# mcu.net
KiCad netlist of a schematic drawn in Altium Designer
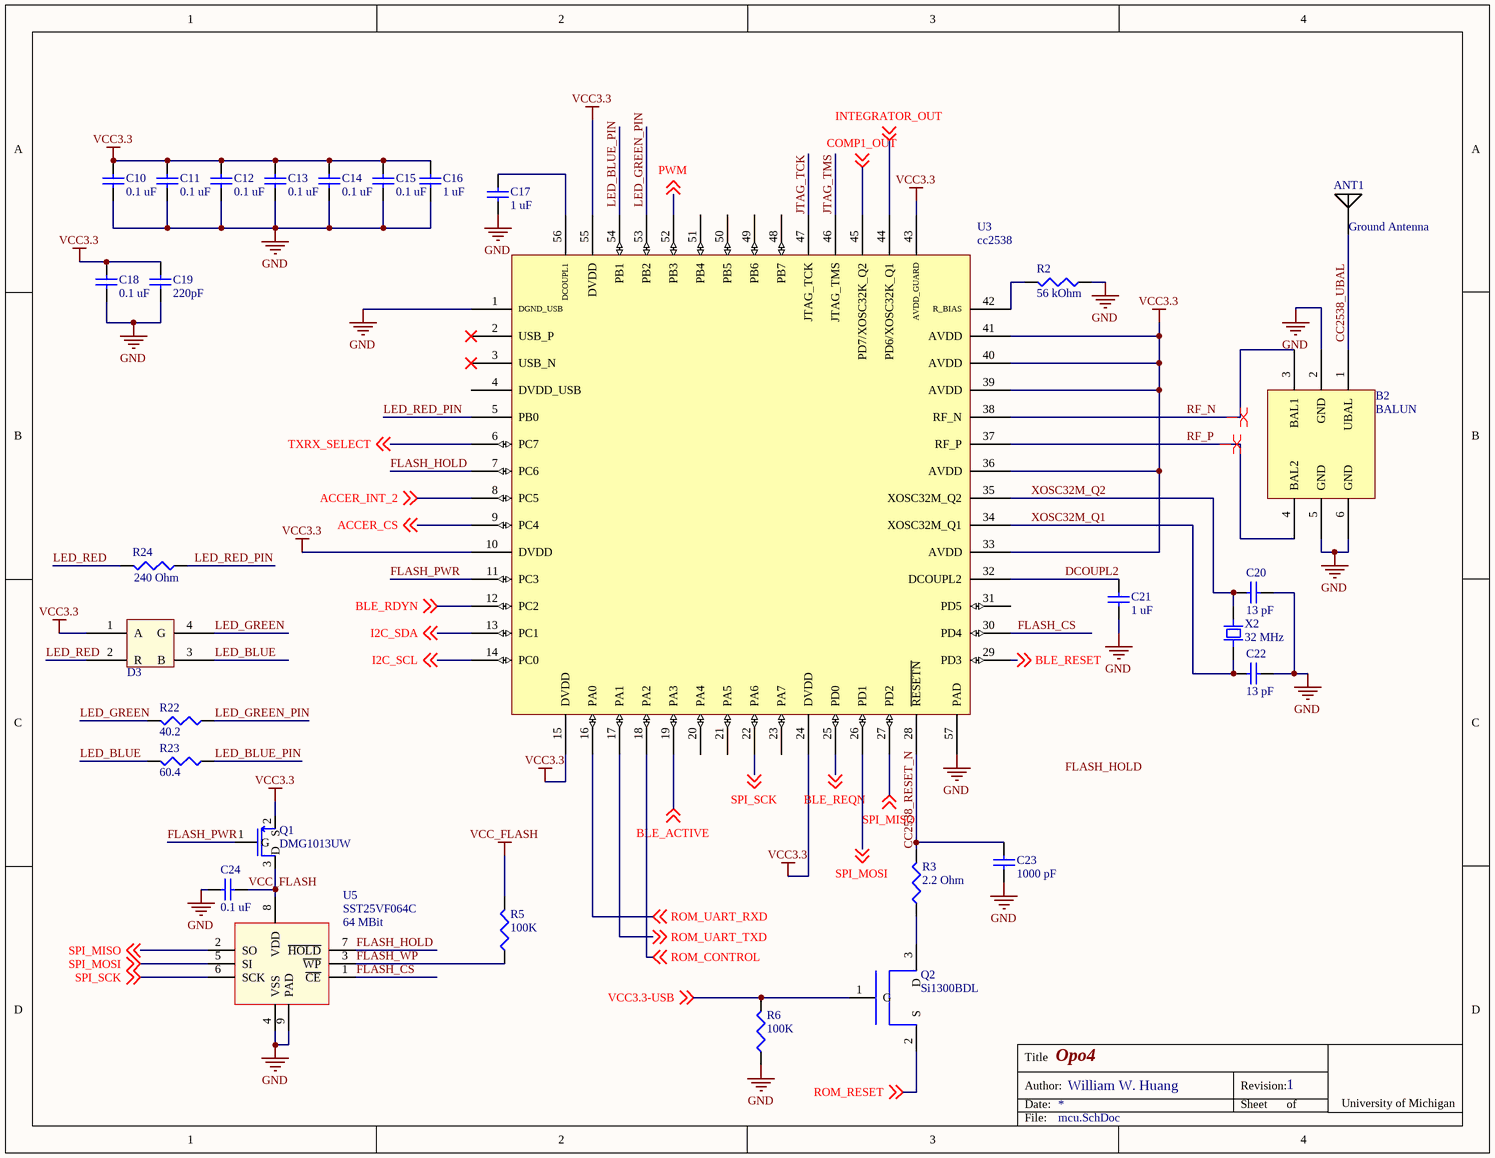
[diagram p0: mcu.SchDoc]

(export (version "E")
  (design (tool "Eeschema 10.0.6"))
  (components
    (comp (ref "ANT1")
      (value "Ground Antenna")
      (footprint "SMD Ground Antenna")
      (description "Molex 2.4 GHz SMD On-Ground Antenna")
      (libsource (lib "opo_general") (part "Molex Antenna"))
    )
    (comp (ref "B2")
      (value "BALUN")
      (footprint "2450BM15A0002")
      (description "Johanson CC253X Balun")
      (fields (field (name "MFR") "Johanson Technology") (field (name "MFR PART NUMBER") "2450BM15A0002"))
      (libsource (lib "opo_general") (part "cc2538_Balun"))
    )
    (comp (ref "C10")
      (value "0.1 uF")
      (footprint "0402")
      (description "Ceramic capacitor, 0.1u, 0402 package")
      (fields (field (name "TOLERANCE") "10%") (field (name "Comment") "Ceramic capacitor"))
      (libsource (lib "rlc") (part "C_0.1u_0402_ceramic"))
    )
    (comp (ref "C11")
      (value "0.1 uF")
      (footprint "0402")
      (description "Ceramic capacitor, 0.1u, 0402 package")
      (fields (field (name "TOLERANCE") "10%") (field (name "Comment") "Ceramic capacitor"))
      (libsource (lib "rlc") (part "C_0.1u_0402_ceramic"))
    )
    (comp (ref "C12")
      (value "0.1 uF")
      (footprint "0402")
      (description "Ceramic capacitor, 0.1u, 0402 package")
      (fields (field (name "TOLERANCE") "10%") (field (name "Comment") "Ceramic capacitor"))
      (libsource (lib "rlc") (part "C_0.1u_0402_ceramic"))
    )
    (comp (ref "C13")
      (value "0.1 uF")
      (footprint "0402")
      (description "Ceramic capacitor, 0.1u, 0402 package")
      (fields (field (name "TOLERANCE") "10%") (field (name "Comment") "Ceramic capacitor"))
      (libsource (lib "rlc") (part "C_0.1u_0402_ceramic"))
    )
    (comp (ref "C14")
      (value "0.1 uF")
      (footprint "0402")
      (description "Ceramic capacitor, 0.1u, 0402 package")
      (fields (field (name "TOLERANCE") "10%") (field (name "Comment") "Ceramic capacitor"))
      (libsource (lib "rlc") (part "C_0.1u_0402_ceramic"))
    )
    (comp (ref "C15")
      (value "0.1 uF")
      (footprint "0402")
      (description "Ceramic capacitor, 0.1u, 0402 package")
      (fields (field (name "TOLERANCE") "10%") (field (name "Comment") "Ceramic capacitor"))
      (libsource (lib "rlc") (part "C_0.1u_0402_ceramic"))
    )
    (comp (ref "C16")
      (value "1 uF")
      (footprint "0402")
      (description "Ceramic capacitor, 1 uF, 0402 package")
      (fields (field (name "TOLERANCE") "10%") (field (name "Comment") "Ceramic capacitor"))
      (libsource (lib "rlc") (part "C_1u_0402_ceramic"))
    )
    (comp (ref "C17")
      (value "1 uF")
      (footprint "0402")
      (description "Ceramic capacitor, 1 uF, 0402 package")
      (fields (field (name "TOLERANCE") "10%") (field (name "Comment") "Ceramic capacitor"))
      (libsource (lib "rlc") (part "C_1u_0402_ceramic"))
    )
    (comp (ref "C18")
      (value "0.1 uF")
      (footprint "0402")
      (description "Ceramic capacitor, 0.1u, 0402 package")
      (fields (field (name "TOLERANCE") "10%") (field (name "Comment") "Ceramic capacitor"))
      (libsource (lib "rlc") (part "C_0.1u_0402_ceramic"))
    )
    (comp (ref "C19")
      (value "220pF")
      (footprint "0402")
      (description "220pF 5% 50 V C0G NP0 0402 ceramic cap")
      (fields (field (name "MFR") "Murata") (field (name "MFR PART NUMBER") "GRM1555C1H221JA01D"))
      (libsource (lib "rlc") (part "C_220pf_0402_ceramic"))
    )
    (comp (ref "C20")
      (value "13 pF")
      (footprint "0402")
      (description "13pf, 50V, 2%, c0G, NP0, 0402, ceramic")
      (fields (field (name "MFR") "Murata") (field (name "MFR PART NUMBER") "GRM1555C1H130GA01D"))
      (libsource (lib "rlc") (part "C_13p_0402"))
    )
    (comp (ref "C21")
      (value "1 uF")
      (footprint "0402")
      (description "Ceramic capacitor, 1 uF, 0402 package")
      (fields (field (name "TOLERANCE") "10%") (field (name "Comment") "Ceramic capacitor"))
      (libsource (lib "rlc") (part "C_1u_0402_ceramic"))
    )
    (comp (ref "C22")
      (value "13 pF")
      (footprint "0402")
      (description "13pf, 50V, 2%, c0G, NP0, 0402, ceramic")
      (fields (field (name "MFR") "Murata") (field (name "MFR PART NUMBER") "GRM1555C1H130GA01D"))
      (libsource (lib "rlc") (part "C_13p_0402"))
    )
    (comp (ref "C23")
      (value "1000 pF")
      (footprint "0402")
      (description "Ceramic capacitor, 1000 pF, 0402 package")
      (fields (field (name "TOLERANCE") "10%") (field (name "Comment") "Ceramic capacitor"))
      (libsource (lib "rlc") (part "C_1000p_0402_ceramic"))
    )
    (comp (ref "C24")
      (value "0.1 uF")
      (footprint "0402")
      (description "Ceramic capacitor, 0.1u, 0402 package")
      (fields (field (name "TOLERANCE") "10%") (field (name "Comment") "Ceramic capacitor"))
      (libsource (lib "rlc") (part "C_0.1u_0402_ceramic"))
    )
    (comp (ref "D3")
      (value "Tri Color LED")
      (footprint "0404")
      (description "LED, RGB, 0404")
      (libsource (lib "rlc") (part "D_LED_RGB_0404"))
    )
    (comp (ref "Q1")
      (value "DMG1013UW")
      (footprint "SC70-3")
      (description "P-CHANNEL ENHANCEMENT MODE MOSFET")
      (libsource (lib "opo_general") (part "DMG1013UW"))
    )
    (comp (ref "Q2")
      (value "Si1300BDL")
      (footprint "SC70-3")
      (description "MOSFET N-CH D-S 20V SC-70-3")
      (libsource (lib "opo_general") (part "Si1300BDL"))
    )
    (comp (ref "R2")
      (value "56 kOhm")
      (footprint "0402")
      (description "56 kOhm, 1%, .0603 W, 0402")
      (fields (field (name "MFR") "Rohm") (field (name "MFR PART NUMBER") "MCR01MRTF5602"))
      (libsource (lib "rlc") (part "R_56K_0402"))
    )
    (comp (ref "R3")
      (value "2.2 Ohm")
      (footprint "0402")
      (description "2.2 Ohm, 1%, .063W, 0402")
      (fields (field (name "MFR") "Vishay Dale") (field (name "MFR PART NUMBER") "CRCW04022R20FKED"))
      (libsource (lib "rlc") (part "R_2.2_0402"))
    )
    (comp (ref "R5")
      (value "100K")
      (footprint "0402")
      (description "Chip resistor, 100K, 0402 package")
      (fields (field (name "TOLERANCE") "1%") (field (name "POWER") "1/16 W"))
      (libsource (lib "rlc") (part "R_100K_0402"))
    )
    (comp (ref "R6")
      (value "100K")
      (footprint "0402")
      (description "Chip resistor, 100K, 0402 package")
      (fields (field (name "TOLERANCE") "1%") (field (name "POWER") "1/16 W"))
      (libsource (lib "rlc") (part "R_100K_0402"))
    )
    (comp (ref "R22")
      (value "40.2")
      (footprint "0201")
      (description "40.2 Ohm 0201 1% Chip Resistor")
      (fields (field (name "Comment") "Chip Resistor"))
      (libsource (lib "rlc") (part "R_40.2_0201"))
    )
    (comp (ref "R23")
      (value "60.4")
      (footprint "0201")
      (description "60.4 Ohm, .05W, 1% 0201 Chip Resistor")
      (fields (field (name "Comment") "Chip resistor"))
      (libsource (lib "rlc") (part "R_60.4_0201"))
    )
    (comp (ref "R24")
      (value "240 Ohm")
      (footprint "0201")
      (description "240 Ohm, 1%, .05W, 0201 Chip Resistor")
      (fields (field (name "Comment") "Chip resistor"))
      (libsource (lib "rlc") (part "R_240_0201"))
    )
    (comp (ref "U3")
      (value "cc2538")
      (footprint "QFN50P800X800X100_HS-57N")
      (description "cc2538 MCU/802.15.4 radio")
      (libsource (lib "opo_general") (part "cc2538"))
    )
    (comp (ref "U5")
      (value "SST25VF064C")
      (footprint "WSON")
      (description "64 Mbit SPI Serial Dual I/O Flash")
      (fields (field (name "CAPACITY") "64 MBit"))
      (libsource (lib "opo_general") (part "SST25VF064C"))
    )
    (comp (ref "X2")
      (value "32 MHz")
      (footprint "FA-128")
      (description "32MHz, 10ppm, 10pF, 60 Ohm")
      (fields (field (name "MFR") "Epson") (field (name "MFR PART NUMBER") "FA-128 32.0000MF20X-K3"))
      (libsource (lib "opo_general") (part "X_32M_FA-128"))
    )
  )
  (nets
    (net (code "1") (name "/CC2538_RESET_N") (class "Default")
      (node (ref "C23") (pin "1") (pintype "passive"))
      (node (ref "R3") (pin "1") (pintype "passive"))
      (node (ref "U3") (pin "28") (pinfunction "~{RESETN}_28") (pintype "passive"))
    )
    (net (code "2") (name "/CC2538_UBAL") (class "Default")
      (node (ref "ANT1") (pin "1") (pintype "passive"))
      (node (ref "B2") (pin "1") (pinfunction "UBAL_1") (pintype "passive"))
    )
    (net (code "3") (name "/DCOUPL2") (class "Default")
      (node (ref "C21") (pin "1") (pintype "passive"))
      (node (ref "U3") (pin "32") (pinfunction "DCOUPL2_32") (pintype "power_in"))
    )
    (net (code "4") (name "/FLASH_CS") (class "Default")
      (node (ref "U3") (pin "30") (pinfunction "PD4_30") (pintype "bidirectional"))
      (node (ref "U5") (pin "1") (pinfunction "~{CE}_1") (pintype "passive"))
    )
    (net (code "5") (name "/FLASH_HOLD") (class "Default")
      (node (ref "U3") (pin "7") (pinfunction "PC6_7") (pintype "bidirectional"))
      (node (ref "U5") (pin "7") (pinfunction "~{HOLD}_7") (pintype "passive"))
    )
    (net (code "6") (name "/FLASH_PWR") (class "Default")
      (node (ref "Q1") (pin "1") (pinfunction "G_1") (pintype "passive"))
      (node (ref "U3") (pin "11") (pinfunction "PC3_11") (pintype "bidirectional"))
    )
    (net (code "7") (name "/FLASH_WP") (class "Default")
      (node (ref "R5") (pin "2") (pintype "passive"))
      (node (ref "U5") (pin "3") (pinfunction "~{WP}_3") (pintype "passive"))
    )
    (net (code "8") (name "/JTAG_TCK") (class "Default")
      (node (ref "U3") (pin "47") (pinfunction "JTAG_TCK_47") (pintype "passive"))
    )
    (net (code "9") (name "/JTAG_TMS") (class "Default")
      (node (ref "U3") (pin "46") (pinfunction "JTAG_TMS_46") (pintype "passive"))
    )
    (net (code "10") (name "/LED_BLUE") (class "Default")
      (node (ref "D3") (pin "3") (pinfunction "B_3") (pintype "passive"))
      (node (ref "R23") (pin "1") (pintype "passive"))
    )
    (net (code "11") (name "/LED_BLUE_PIN") (class "Default")
      (node (ref "R23") (pin "2") (pintype "passive"))
      (node (ref "U3") (pin "54") (pinfunction "PB1_54") (pintype "bidirectional"))
    )
    (net (code "12") (name "/LED_GREEN") (class "Default")
      (node (ref "D3") (pin "4") (pinfunction "G_4") (pintype "passive"))
      (node (ref "R22") (pin "1") (pintype "passive"))
    )
    (net (code "13") (name "/LED_GREEN_PIN") (class "Default")
      (node (ref "R22") (pin "2") (pintype "passive"))
      (node (ref "U3") (pin "53") (pinfunction "PB2_53") (pintype "bidirectional"))
    )
    (net (code "14") (name "/LED_RED") (class "Default")
      (node (ref "D3") (pin "2") (pinfunction "R_2") (pintype "passive"))
      (node (ref "R24") (pin "1") (pintype "passive"))
    )
    (net (code "15") (name "/LED_RED_PIN") (class "Default")
      (node (ref "R24") (pin "2") (pintype "passive"))
      (node (ref "U3") (pin "5") (pinfunction "PB0_5") (pintype "passive"))
    )
    (net (code "16") (name "/RF_N") (class "Default")
      (node (ref "B2") (pin "3") (pinfunction "BAL1_3") (pintype "passive"))
      (node (ref "U3") (pin "38") (pinfunction "RF_N_38") (pintype "passive"))
    )
    (net (code "17") (name "/RF_P") (class "Default")
      (node (ref "B2") (pin "4") (pinfunction "BAL2_4") (pintype "passive"))
      (node (ref "U3") (pin "37") (pinfunction "RF_P_37") (pintype "passive"))
    )
    (net (code "18") (name "/XOSC32M_Q1") (class "Default")
      (node (ref "C22") (pin "2") (pintype "passive"))
      (node (ref "U3") (pin "34") (pinfunction "XOSC32M_Q1_34") (pintype "passive"))
      (node (ref "X2") (pin "3") (pintype "passive"))
    )
    (net (code "19") (name "/XOSC32M_Q2") (class "Default")
      (node (ref "C20") (pin "1") (pintype "passive"))
      (node (ref "U3") (pin "35") (pinfunction "XOSC32M_Q2_35") (pintype "passive"))
      (node (ref "X2") (pin "1") (pintype "passive"))
    )
    (net (code "20") (name "ACCER_CS") (class "Default")
      (node (ref "U3") (pin "9") (pinfunction "PC4_9") (pintype "bidirectional"))
    )
    (net (code "21") (name "ACCER_INT_2") (class "Default")
      (node (ref "U3") (pin "8") (pinfunction "PC5_8") (pintype "bidirectional"))
    )
    (net (code "22") (name "BLE_ACTIVE") (class "Default")
      (node (ref "U3") (pin "19") (pinfunction "PA3_19") (pintype "bidirectional"))
    )
    (net (code "23") (name "BLE_RDYN") (class "Default")
      (node (ref "U3") (pin "12") (pinfunction "PC2_12") (pintype "bidirectional"))
    )
    (net (code "24") (name "BLE_REQN") (class "Default")
      (node (ref "U3") (pin "25") (pinfunction "PD0_25") (pintype "bidirectional"))
    )
    (net (code "25") (name "BLE_RESET") (class "Default")
      (node (ref "U3") (pin "29") (pinfunction "PD3_29") (pintype "bidirectional"))
    )
    (net (code "26") (name "COMP1_OUT") (class "Default")
      (node (ref "U3") (pin "45") (pinfunction "PD7/XOSC32K_Q2_45") (pintype "passive"))
    )
    (net (code "27") (name "GND") (class "Default")
      (node (ref "B2") (pin "2") (pinfunction "GND_2") (pintype "passive"))
      (node (ref "B2") (pin "5") (pinfunction "GND_5") (pintype "passive"))
      (node (ref "B2") (pin "6") (pinfunction "GND_6") (pintype "passive"))
      (node (ref "C10") (pin "2") (pintype "passive"))
      (node (ref "C11") (pin "2") (pintype "passive"))
      (node (ref "C12") (pin "2") (pintype "passive"))
      (node (ref "C13") (pin "2") (pintype "passive"))
      (node (ref "C14") (pin "2") (pintype "passive"))
      (node (ref "C15") (pin "2") (pintype "passive"))
      (node (ref "C16") (pin "2") (pintype "passive"))
      (node (ref "C17") (pin "2") (pintype "passive"))
      (node (ref "C18") (pin "2") (pintype "passive"))
      (node (ref "C19") (pin "2") (pintype "passive"))
      (node (ref "C20") (pin "2") (pintype "passive"))
      (node (ref "C21") (pin "2") (pintype "passive"))
      (node (ref "C22") (pin "1") (pintype "passive"))
      (node (ref "C23") (pin "2") (pintype "passive"))
      (node (ref "C24") (pin "1") (pintype "passive"))
      (node (ref "R2") (pin "2") (pintype "passive"))
      (node (ref "R6") (pin "2") (pintype "passive"))
      (node (ref "U3") (pin "1") (pinfunction "DGND_USB_1") (pintype "passive"))
      (node (ref "U3") (pin "57") (pinfunction "PAD_57") (pintype "passive"))
      (node (ref "U5") (pin "4") (pinfunction "VSS_4") (pintype "passive"))
      (node (ref "U5") (pin "9") (pinfunction "PAD_9") (pintype "passive"))
    )
    (net (code "28") (name "I2C_SCL") (class "Default")
      (node (ref "U3") (pin "14") (pinfunction "PC0_14") (pintype "bidirectional"))
    )
    (net (code "29") (name "I2C_SDA") (class "Default")
      (node (ref "U3") (pin "13") (pinfunction "PC1_13") (pintype "bidirectional"))
    )
    (net (code "30") (name "INTEGRATOR_OUT") (class "Default")
      (node (ref "U3") (pin "44") (pinfunction "PD6/XOSC32K_Q1_44") (pintype "passive"))
    )
    (net (code "31") (name "Net-(Q2-D)") (class "Default")
      (node (ref "Q2") (pin "3") (pinfunction "D_3") (pintype "passive"))
      (node (ref "R3") (pin "2") (pintype "passive"))
    )
    (net (code "32") (name "Net-(U3-DCOUPL1)") (class "Default")
      (node (ref "C17") (pin "1") (pintype "passive"))
      (node (ref "U3") (pin "56") (pinfunction "DCOUPL1_56") (pintype "power_in"))
    )
    (net (code "33") (name "Net-(U3-R_BIAS)") (class "Default")
      (node (ref "R2") (pin "1") (pintype "passive"))
      (node (ref "U3") (pin "42") (pinfunction "R_BIAS_42") (pintype "passive"))
    )
    (net (code "34") (name "PWM") (class "Default")
      (node (ref "U3") (pin "52") (pinfunction "PB3_52") (pintype "bidirectional"))
    )
    (net (code "35") (name "ROM_CONTROL") (class "Default")
      (node (ref "U3") (pin "18") (pinfunction "PA2_18") (pintype "bidirectional"))
    )
    (net (code "36") (name "ROM_RESET") (class "Default")
      (node (ref "Q2") (pin "2") (pinfunction "S_2") (pintype "passive"))
    )
    (net (code "37") (name "ROM_UART_RXD") (class "Default")
      (node (ref "U3") (pin "16") (pinfunction "PA0_16") (pintype "bidirectional"))
    )
    (net (code "38") (name "ROM_UART_TXD") (class "Default")
      (node (ref "U3") (pin "17") (pinfunction "PA1_17") (pintype "bidirectional"))
    )
    (net (code "39") (name "SPI_MISO") (class "Default")
      (node (ref "U3") (pin "27") (pinfunction "PD2_27") (pintype "bidirectional"))
      (node (ref "U5") (pin "2") (pinfunction "SO_2") (pintype "passive"))
    )
    (net (code "40") (name "SPI_MOSI") (class "Default")
      (node (ref "U3") (pin "26") (pinfunction "PD1_26") (pintype "bidirectional"))
      (node (ref "U5") (pin "5") (pinfunction "SI_5") (pintype "passive"))
    )
    (net (code "41") (name "SPI_SCK") (class "Default")
      (node (ref "U3") (pin "22") (pinfunction "PA6_22") (pintype "bidirectional"))
      (node (ref "U5") (pin "6") (pinfunction "SCK_6") (pintype "passive"))
    )
    (net (code "42") (name "TXRX_SELECT") (class "Default")
      (node (ref "U3") (pin "6") (pinfunction "PC7_6") (pintype "bidirectional"))
    )
    (net (code "43") (name "VCC3.3") (class "Default")
      (node (ref "C10") (pin "1") (pintype "passive"))
      (node (ref "C11") (pin "1") (pintype "passive"))
      (node (ref "C12") (pin "1") (pintype "passive"))
      (node (ref "C13") (pin "1") (pintype "passive"))
      (node (ref "C14") (pin "1") (pintype "passive"))
      (node (ref "C15") (pin "1") (pintype "passive"))
      (node (ref "C16") (pin "1") (pintype "passive"))
      (node (ref "C18") (pin "1") (pintype "passive"))
      (node (ref "C19") (pin "1") (pintype "passive"))
      (node (ref "D3") (pin "1") (pinfunction "A_1") (pintype "passive"))
      (node (ref "Q1") (pin "2") (pinfunction "S_2") (pintype "passive"))
      (node (ref "U3") (pin "10") (pinfunction "DVDD_10") (pintype "power_in"))
      (node (ref "U3") (pin "15") (pinfunction "DVDD_15") (pintype "power_in"))
      (node (ref "U3") (pin "24") (pinfunction "DVDD_24") (pintype "power_in"))
      (node (ref "U3") (pin "33") (pinfunction "AVDD_33") (pintype "power_in"))
      (node (ref "U3") (pin "36") (pinfunction "AVDD_36") (pintype "power_in"))
      (node (ref "U3") (pin "39") (pinfunction "AVDD_39") (pintype "power_in"))
      (node (ref "U3") (pin "40") (pinfunction "AVDD_40") (pintype "power_in"))
      (node (ref "U3") (pin "41") (pinfunction "AVDD_41") (pintype "power_in"))
      (node (ref "U3") (pin "43") (pinfunction "AVDD_GUARD_43") (pintype "power_in"))
      (node (ref "U3") (pin "55") (pinfunction "DVDD_55") (pintype "power_in"))
    )
    (net (code "44") (name "VCC3.3-USB") (class "Default")
      (node (ref "Q2") (pin "1") (pinfunction "G_1") (pintype "passive"))
      (node (ref "R6") (pin "1") (pintype "passive"))
    )
    (net (code "45") (name "VCC_FLASH") (class "Default")
      (node (ref "C24") (pin "2") (pintype "passive"))
      (node (ref "Q1") (pin "3") (pinfunction "D_3") (pintype "passive"))
      (node (ref "R5") (pin "1") (pintype "passive"))
      (node (ref "U5") (pin "8") (pinfunction "VDD_8") (pintype "passive"))
    )
    (net (code "46") (name "unconnected-(U3-DVDD_USB-Pad4)") (class "Default")
      (node (ref "U3") (pin "4") (pinfunction "DVDD_USB_4") (pintype "passive"))
    )
    (net (code "47") (name "unconnected-(U3-PA4-Pad20)") (class "Default")
      (node (ref "U3") (pin "20") (pinfunction "PA4_20") (pintype "bidirectional"))
    )
    (net (code "48") (name "unconnected-(U3-PA5-Pad21)") (class "Default")
      (node (ref "U3") (pin "21") (pinfunction "PA5_21") (pintype "bidirectional"))
    )
    (net (code "49") (name "unconnected-(U3-PA7-Pad23)") (class "Default")
      (node (ref "U3") (pin "23") (pinfunction "PA7_23") (pintype "bidirectional"))
    )
    (net (code "50") (name "unconnected-(U3-PB4-Pad51)") (class "Default")
      (node (ref "U3") (pin "51") (pinfunction "PB4_51") (pintype "bidirectional"))
    )
    (net (code "51") (name "unconnected-(U3-PB5-Pad50)") (class "Default")
      (node (ref "U3") (pin "50") (pinfunction "PB5_50") (pintype "bidirectional"))
    )
    (net (code "52") (name "unconnected-(U3-PB6-Pad49)") (class "Default")
      (node (ref "U3") (pin "49") (pinfunction "PB6_49") (pintype "bidirectional"))
    )
    (net (code "53") (name "unconnected-(U3-PB7-Pad48)") (class "Default")
      (node (ref "U3") (pin "48") (pinfunction "PB7_48") (pintype "bidirectional"))
    )
    (net (code "54") (name "unconnected-(U3-PD5-Pad31)") (class "Default")
      (node (ref "U3") (pin "31") (pinfunction "PD5_31") (pintype "bidirectional"))
    )
    (net (code "55") (name "unconnected-(U3-USB_N-Pad3)") (class "Default")
      (node (ref "U3") (pin "3") (pinfunction "USB_N_3") (pintype "passive+no_connect"))
    )
    (net (code "56") (name "unconnected-(U3-USB_P-Pad2)") (class "Default")
      (node (ref "U3") (pin "2") (pinfunction "USB_P_2") (pintype "passive+no_connect"))
    )
  )
)
